# Top.net
KiCad netlist of a schematic drawn in Altium Designer
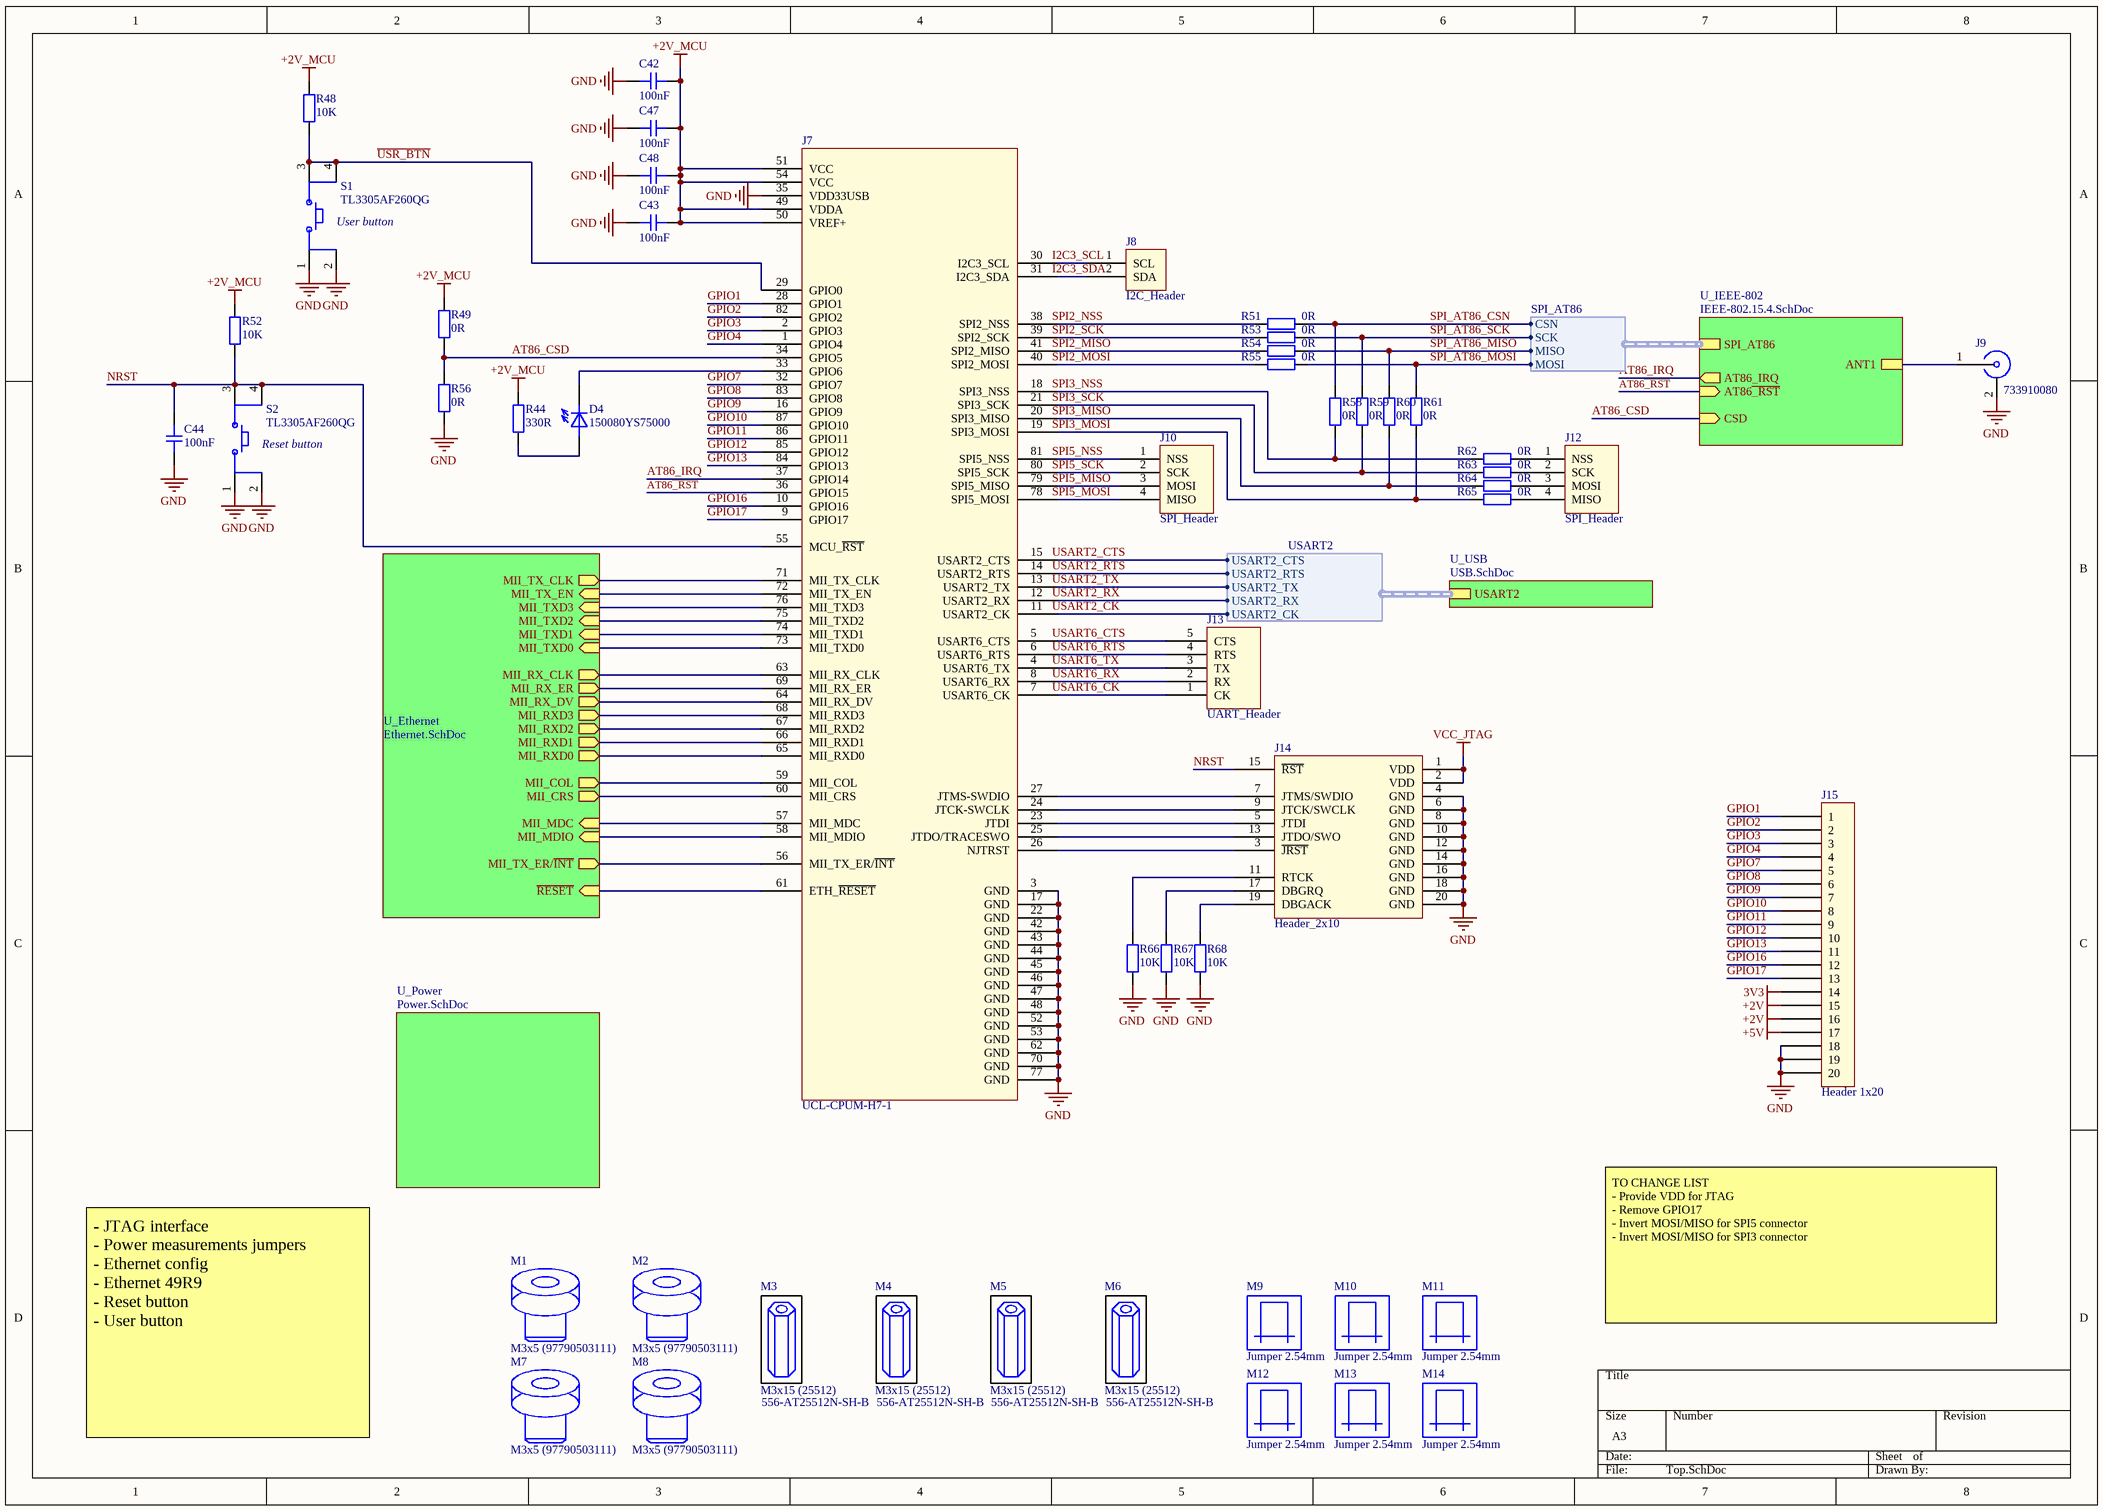
[diagram p0: Top.SchDoc]

(export (version "E")
  (design (tool "Eeschema 10.0.6"))
  (components
    (comp (ref "C42")
      (value "100nF")
      (footprint "Capacitor-0603")
      (fields (field (name "Comment") "C-100nF-0603"))
      (libsource (lib "Components") (part "C-100nF-0603"))
    )
    (comp (ref "C43")
      (value "100nF")
      (footprint "Capacitor-0603")
      (fields (field (name "Comment") "C-100nF-0603"))
      (libsource (lib "Components") (part "C-100nF-0603"))
    )
    (comp (ref "C44")
      (value "100nF")
      (footprint "Capacitor-0603")
      (fields (field (name "Comment") "C-100nF-0603"))
      (libsource (lib "Components") (part "C-100nF-0603"))
    )
    (comp (ref "C47")
      (value "100nF")
      (footprint "Capacitor-0603")
      (fields (field (name "Comment") "C-100nF-0603"))
      (libsource (lib "Components") (part "C-100nF-0603"))
    )
    (comp (ref "C48")
      (value "100nF")
      (footprint "Capacitor-0603")
      (fields (field (name "Comment") "C-100nF-0603"))
      (libsource (lib "Components") (part "C-100nF-0603"))
    )
    (comp (ref "D4")
      (value "150080YS75000")
      (footprint "150080YS75000")
      (libsource (lib "Components") (part "150080YS75000"))
    )
    (comp (ref "J7")
      (value "UCL-CPUM-H7-1")
      (footprint "UCL-CPUM-H7-1")
      (libsource (lib "Components") (part "UCL-CPUM-H7-1"))
    )
    (comp (ref "J8")
      (value "I2C_Header")
      (footprint "I2C_header")
      (libsource (lib "Components") (part "I2C_Header"))
    )
    (comp (ref "J9")
      (value "733910080")
      (footprint "SMA_733910080")
      (libsource (lib "Components") (part "SMA_733910080"))
    )
    (comp (ref "J10")
      (value "SPI_Header")
      (footprint "SPI_Header")
      (libsource (lib "Components") (part "SPI_Header"))
    )
    (comp (ref "J12")
      (value "SPI_Header")
      (footprint "SPI_Header")
      (libsource (lib "Components") (part "SPI_Header"))
    )
    (comp (ref "J13")
      (value "UART_Header")
      (footprint "UART_Header")
      (libsource (lib "Components") (part "UART_Header"))
    )
    (comp (ref "J14")
      (value "Header_2x10")
      (footprint "JTAG_Header")
      (libsource (lib "Components") (part "JTAG_Header"))
    )
    (comp (ref "J15")
      (value "Header 1x20")
      (footprint "GPIO_Header")
      (libsource (lib "Components") (part "GPIO_Header"))
    )
    (comp (ref "M1")
      (value "M3x5 (97790503111)")
      (footprint "Screw_M3")
      (libsource (lib "Components") (part "Screw_M3x5"))
    )
    (comp (ref "M2")
      (value "M3x5 (97790503111)")
      (footprint "Screw_M3")
      (libsource (lib "Components") (part "Screw_M3x5"))
    )
    (comp (ref "M3")
      (value "M3x15 (25512)")
      (fields (field (name "SUPPLIER PART NUMBER 1") "556-AT25512N-SH-B"))
      (libsource (lib "Components") (part "Standoff_hex_M3_15mm_25512"))
    )
    (comp (ref "M4")
      (value "M3x15 (25512)")
      (fields (field (name "SUPPLIER PART NUMBER 1") "556-AT25512N-SH-B"))
      (libsource (lib "Components") (part "Standoff_hex_M3_15mm_25512"))
    )
    (comp (ref "M5")
      (value "M3x15 (25512)")
      (fields (field (name "SUPPLIER PART NUMBER 1") "556-AT25512N-SH-B"))
      (libsource (lib "Components") (part "Standoff_hex_M3_15mm_25512"))
    )
    (comp (ref "M6")
      (value "M3x15 (25512)")
      (fields (field (name "SUPPLIER PART NUMBER 1") "556-AT25512N-SH-B"))
      (libsource (lib "Components") (part "Standoff_hex_M3_15mm_25512"))
    )
    (comp (ref "M7")
      (value "M3x5 (97790503111)")
      (footprint "Screw_M3")
      (libsource (lib "Components") (part "Screw_M3x5"))
    )
    (comp (ref "M8")
      (value "M3x5 (97790503111)")
      (footprint "Screw_M3")
      (libsource (lib "Components") (part "Screw_M3x5"))
    )
    (comp (ref "M9") (value "Jumper 2.54mm") (libsource (lib "Components") (part "QPC02SXGN-RC")))
    (comp (ref "M10") (value "Jumper 2.54mm") (libsource (lib "Components") (part "QPC02SXGN-RC")))
    (comp (ref "M11") (value "Jumper 2.54mm") (libsource (lib "Components") (part "QPC02SXGN-RC")))
    (comp (ref "M12") (value "Jumper 2.54mm") (libsource (lib "Components") (part "QPC02SXGN-RC")))
    (comp (ref "M13") (value "Jumper 2.54mm") (libsource (lib "Components") (part "QPC02SXGN-RC")))
    (comp (ref "M14") (value "Jumper 2.54mm") (libsource (lib "Components") (part "QPC02SXGN-RC")))
    (comp (ref "R44")
      (value "330R")
      (footprint "Resistor-0603")
      (fields (field (name "Comment") "R-330R-0603"))
      (libsource (lib "Components") (part "R-330R-0603"))
    )
    (comp (ref "R48")
      (value "10K")
      (footprint "Resistor-0603")
      (fields (field (name "Comment") "R-10K-0603"))
      (libsource (lib "Components") (part "R-10K-0603"))
    )
    (comp (ref "R49")
      (value "0R")
      (footprint "Resistor-0603")
      (fields (field (name "Comment") "R-0R-0603"))
      (libsource (lib "Components") (part "R-0R-0603"))
    )
    (comp (ref "R51")
      (value "0R")
      (footprint "Resistor-0603")
      (fields (field (name "Comment") "R-0R-0603"))
      (libsource (lib "Components") (part "R-0R-0603"))
    )
    (comp (ref "R52")
      (value "10K")
      (footprint "Resistor-0603")
      (fields (field (name "Comment") "R-10K-0603"))
      (libsource (lib "Components") (part "R-10K-0603"))
    )
    (comp (ref "R53")
      (value "0R")
      (footprint "Resistor-0603")
      (fields (field (name "Comment") "R-0R-0603"))
      (libsource (lib "Components") (part "R-0R-0603"))
    )
    (comp (ref "R54")
      (value "0R")
      (footprint "Resistor-0603")
      (fields (field (name "Comment") "R-0R-0603"))
      (libsource (lib "Components") (part "R-0R-0603"))
    )
    (comp (ref "R55")
      (value "0R")
      (footprint "Resistor-0603")
      (fields (field (name "Comment") "R-0R-0603"))
      (libsource (lib "Components") (part "R-0R-0603"))
    )
    (comp (ref "R56")
      (value "0R")
      (footprint "Resistor-0603")
      (fields (field (name "Comment") "R-0R-0603"))
      (libsource (lib "Components") (part "R-0R-0603"))
    )
    (comp (ref "R58")
      (value "0R")
      (footprint "Resistor-0603")
      (fields (field (name "Comment") "R-0R-0603"))
      (libsource (lib "Components") (part "R-0R-0603"))
    )
    (comp (ref "R59")
      (value "0R")
      (footprint "Resistor-0603")
      (fields (field (name "Comment") "R-0R-0603"))
      (libsource (lib "Components") (part "R-0R-0603"))
    )
    (comp (ref "R60")
      (value "0R")
      (footprint "Resistor-0603")
      (fields (field (name "Comment") "R-0R-0603"))
      (libsource (lib "Components") (part "R-0R-0603"))
    )
    (comp (ref "R61")
      (value "0R")
      (footprint "Resistor-0603")
      (fields (field (name "Comment") "R-0R-0603"))
      (libsource (lib "Components") (part "R-0R-0603"))
    )
    (comp (ref "R62")
      (value "0R")
      (footprint "Resistor-0603")
      (fields (field (name "Comment") "R-0R-0603"))
      (libsource (lib "Components") (part "R-0R-0603"))
    )
    (comp (ref "R63")
      (value "0R")
      (footprint "Resistor-0603")
      (fields (field (name "Comment") "R-0R-0603"))
      (libsource (lib "Components") (part "R-0R-0603"))
    )
    (comp (ref "R64")
      (value "0R")
      (footprint "Resistor-0603")
      (fields (field (name "Comment") "R-0R-0603"))
      (libsource (lib "Components") (part "R-0R-0603"))
    )
    (comp (ref "R65")
      (value "0R")
      (footprint "Resistor-0603")
      (fields (field (name "Comment") "R-0R-0603"))
      (libsource (lib "Components") (part "R-0R-0603"))
    )
    (comp (ref "R66")
      (value "10K")
      (footprint "Resistor-0603")
      (fields (field (name "Comment") "R-10K-0603"))
      (libsource (lib "Components") (part "R-10K-0603"))
    )
    (comp (ref "R67")
      (value "10K")
      (footprint "Resistor-0603")
      (fields (field (name "Comment") "R-10K-0603"))
      (libsource (lib "Components") (part "R-10K-0603"))
    )
    (comp (ref "R68")
      (value "10K")
      (footprint "Resistor-0603")
      (fields (field (name "Comment") "R-10K-0603"))
      (libsource (lib "Components") (part "R-10K-0603"))
    )
    (comp (ref "S1")
      (value "TL3305AF260QG")
      (footprint "TL3305AF260QG")
      (libsource (lib "Components") (part "TL3305AF260QG"))
    )
    (comp (ref "S2")
      (value "TL3305AF260QG")
      (footprint "TL3305AF260QG")
      (libsource (lib "Components") (part "TL3305AF260QG"))
    )
  )
  (nets
    (net (code "3") (name "+2V") (class "Default")
      (node (ref "J15") (pin "15") (pinfunction "15_15") (pintype "passive"))
      (node (ref "J15") (pin "16") (pinfunction "16_16") (pintype "passive"))
    )
    (net (code "4") (name "+2V_MCU") (class "Default")
      (node (ref "C42") (pin "2") (pinfunction "2_2") (pintype "passive"))
      (node (ref "C43") (pin "2") (pinfunction "2_2") (pintype "passive"))
      (node (ref "C47") (pin "2") (pinfunction "2_2") (pintype "passive"))
      (node (ref "C48") (pin "2") (pinfunction "2_2") (pintype "passive"))
      (node (ref "J7") (pin "49") (pinfunction "VDDA_49") (pintype "passive"))
      (node (ref "J7") (pin "50") (pinfunction "VREF+_50") (pintype "passive"))
      (node (ref "J7") (pin "51") (pinfunction "VCC_51") (pintype "passive"))
      (node (ref "J7") (pin "54") (pinfunction "VCC_54") (pintype "passive"))
      (node (ref "R44") (pin "2") (pinfunction "2_2") (pintype "passive"))
      (node (ref "R48") (pin "2") (pinfunction "2_2") (pintype "passive"))
      (node (ref "R49") (pin "2") (pinfunction "2_2") (pintype "passive"))
      (node (ref "R52") (pin "2") (pinfunction "2_2") (pintype "passive"))
    )
    (net (code "5") (name "+5V") (class "Default")
      (node (ref "J15") (pin "17") (pinfunction "17_17") (pintype "passive"))
    )
    (net (code "6") (name "/ANT1") (class "Default")
      (node (ref "J9") (pin "1") (pinfunction "SIG_1") (pintype "passive"))
    )
    (net (code "7") (name "/AT86_CSD") (class "Default")
      (node (ref "J7") (pin "34") (pinfunction "GPIO5_34") (pintype "passive"))
      (node (ref "R49") (pin "1") (pinfunction "1_1") (pintype "passive"))
      (node (ref "R56") (pin "2") (pinfunction "2_2") (pintype "passive"))
    )
    (net (code "8") (name "/AT86_IRQ") (class "Default")
      (node (ref "J7") (pin "37") (pinfunction "GPIO14_37") (pintype "passive"))
    )
    (net (code "9") (name "/AT86~{_RST}") (class "Default")
      (node (ref "J7") (pin "36") (pinfunction "GPIO15_36") (pintype "passive"))
    )
    (net (code "10") (name "/GPIO1") (class "Default")
      (node (ref "J15") (pin "1") (pinfunction "1_1") (pintype "passive"))
      (node (ref "J7") (pin "28") (pinfunction "GPIO1_28") (pintype "passive"))
    )
    (net (code "11") (name "/GPIO2") (class "Default")
      (node (ref "J15") (pin "2") (pinfunction "2_2") (pintype "passive"))
      (node (ref "J7") (pin "82") (pinfunction "GPIO2_82") (pintype "passive"))
    )
    (net (code "12") (name "/GPIO3") (class "Default")
      (node (ref "J15") (pin "3") (pinfunction "3_3") (pintype "passive"))
      (node (ref "J7") (pin "2") (pinfunction "GPIO3_2") (pintype "passive"))
    )
    (net (code "13") (name "/GPIO4") (class "Default")
      (node (ref "J15") (pin "4") (pinfunction "4_4") (pintype "passive"))
      (node (ref "J7") (pin "1") (pinfunction "GPIO4_1") (pintype "passive"))
    )
    (net (code "14") (name "/GPIO7") (class "Default")
      (node (ref "J15") (pin "5") (pinfunction "5_5") (pintype "passive"))
      (node (ref "J7") (pin "32") (pinfunction "GPIO7_32") (pintype "passive"))
    )
    (net (code "15") (name "/GPIO8") (class "Default")
      (node (ref "J15") (pin "6") (pinfunction "6_6") (pintype "passive"))
      (node (ref "J7") (pin "83") (pinfunction "GPIO8_83") (pintype "passive"))
    )
    (net (code "16") (name "/GPIO9") (class "Default")
      (node (ref "J15") (pin "7") (pinfunction "7_7") (pintype "passive"))
      (node (ref "J7") (pin "16") (pinfunction "GPIO9_16") (pintype "passive"))
    )
    (net (code "17") (name "/GPIO10") (class "Default")
      (node (ref "J15") (pin "8") (pinfunction "8_8") (pintype "passive"))
      (node (ref "J7") (pin "87") (pinfunction "GPIO10_87") (pintype "passive"))
    )
    (net (code "18") (name "/GPIO11") (class "Default")
      (node (ref "J15") (pin "9") (pinfunction "9_9") (pintype "passive"))
      (node (ref "J7") (pin "86") (pinfunction "GPIO11_86") (pintype "passive"))
    )
    (net (code "19") (name "/GPIO12") (class "Default")
      (node (ref "J15") (pin "10") (pinfunction "10_10") (pintype "passive"))
      (node (ref "J7") (pin "85") (pinfunction "GPIO12_85") (pintype "passive"))
    )
    (net (code "20") (name "/GPIO13") (class "Default")
      (node (ref "J15") (pin "11") (pinfunction "11_11") (pintype "passive"))
      (node (ref "J7") (pin "84") (pinfunction "GPIO13_84") (pintype "passive"))
    )
    (net (code "21") (name "/GPIO16") (class "Default")
      (node (ref "J15") (pin "12") (pinfunction "12_12") (pintype "passive"))
      (node (ref "J7") (pin "10") (pinfunction "GPIO16_10") (pintype "passive"))
    )
    (net (code "22") (name "/GPIO17") (class "Default")
      (node (ref "J15") (pin "13") (pinfunction "13_13") (pintype "passive"))
      (node (ref "J7") (pin "9") (pinfunction "GPIO17_9") (pintype "passive"))
    )
    (net (code "25") (name "/MII_COL") (class "Default")
      (node (ref "J7") (pin "59") (pinfunction "MII_COL_59") (pintype "passive"))
    )
    (net (code "26") (name "/MII_CRS") (class "Default")
      (node (ref "J7") (pin "60") (pinfunction "MII_CRS_60") (pintype "passive"))
    )
    (net (code "27") (name "/MII_MDC") (class "Default")
      (node (ref "J7") (pin "57") (pinfunction "MII_MDC_57") (pintype "passive"))
    )
    (net (code "28") (name "/MII_MDIO") (class "Default")
      (node (ref "J7") (pin "58") (pinfunction "MII_MDIO_58") (pintype "passive"))
    )
    (net (code "29") (name "/MII_RXD0") (class "Default")
      (node (ref "J7") (pin "65") (pinfunction "MII_RXD0_65") (pintype "passive"))
    )
    (net (code "30") (name "/MII_RXD1") (class "Default")
      (node (ref "J7") (pin "66") (pinfunction "MII_RXD1_66") (pintype "passive"))
    )
    (net (code "31") (name "/MII_RXD2") (class "Default")
      (node (ref "J7") (pin "67") (pinfunction "MII_RXD2_67") (pintype "passive"))
    )
    (net (code "32") (name "/MII_RXD3") (class "Default")
      (node (ref "J7") (pin "68") (pinfunction "MII_RXD3_68") (pintype "passive"))
    )
    (net (code "33") (name "/MII_RX_CLK") (class "Default")
      (node (ref "J7") (pin "63") (pinfunction "MII_RX_CLK_63") (pintype "passive"))
    )
    (net (code "34") (name "/MII_RX_DV") (class "Default")
      (node (ref "J7") (pin "64") (pinfunction "MII_RX_DV_64") (pintype "passive"))
    )
    (net (code "35") (name "/MII_RX_ER") (class "Default")
      (node (ref "J7") (pin "69") (pinfunction "MII_RX_ER_69") (pintype "passive"))
    )
    (net (code "36") (name "/MII_TXD0") (class "Default")
      (node (ref "J7") (pin "73") (pinfunction "MII_TXD0_73") (pintype "passive"))
    )
    (net (code "37") (name "/MII_TXD1") (class "Default")
      (node (ref "J7") (pin "74") (pinfunction "MII_TXD1_74") (pintype "passive"))
    )
    (net (code "38") (name "/MII_TXD2") (class "Default")
      (node (ref "J7") (pin "75") (pinfunction "MII_TXD2_75") (pintype "passive"))
    )
    (net (code "39") (name "/MII_TXD3") (class "Default")
      (node (ref "J7") (pin "76") (pinfunction "MII_TXD3_76") (pintype "passive"))
    )
    (net (code "40") (name "/MII_TX_CLK") (class "Default")
      (node (ref "J7") (pin "71") (pinfunction "MII_TX_CLK_71") (pintype "passive"))
    )
    (net (code "41") (name "/MII_TX_EN") (class "Default")
      (node (ref "J7") (pin "72") (pinfunction "MII_TX_EN_72") (pintype "passive"))
    )
    (net (code "42") (name "/MII_TX_ER{slash}~{INT}") (class "Default")
      (node (ref "J7") (pin "56") (pinfunction "MII_TX_ER/~{INT}_56") (pintype "passive"))
    )
    (net (code "43") (name "/NRST") (class "Default")
      (node (ref "C44") (pin "2") (pinfunction "2_2") (pintype "passive"))
      (node (ref "J14") (pin "15") (pinfunction "~{RST}_15") (pintype "passive"))
      (node (ref "J7") (pin "55") (pinfunction "MCU_~{RST}_55") (pintype "passive"))
      (node (ref "R52") (pin "1") (pinfunction "1_1") (pintype "passive"))
      (node (ref "S2") (pin "3") (pinfunction "3_3") (pintype "passive"))
      (node (ref "S2") (pin "4") (pinfunction "4_4") (pintype "passive"))
    )
    (net (code "56") (name "/SPI_AT86_CSN") (class "Default")
      (node (ref "R51") (pin "2") (pinfunction "2_2") (pintype "passive"))
      (node (ref "R58") (pin "2") (pinfunction "2_2") (pintype "passive"))
    )
    (net (code "57") (name "/SPI_AT86_MISO") (class "Default")
      (node (ref "R54") (pin "2") (pinfunction "2_2") (pintype "passive"))
      (node (ref "R60") (pin "2") (pinfunction "2_2") (pintype "passive"))
    )
    (net (code "58") (name "/SPI_AT86_MOSI") (class "Default")
      (node (ref "R55") (pin "2") (pinfunction "2_2") (pintype "passive"))
      (node (ref "R61") (pin "2") (pinfunction "2_2") (pintype "passive"))
    )
    (net (code "59") (name "/SPI_AT86_SCK") (class "Default")
      (node (ref "R53") (pin "2") (pinfunction "2_2") (pintype "passive"))
      (node (ref "R59") (pin "2") (pinfunction "2_2") (pintype "passive"))
    )
    (net (code "72") (name "/~{RESET}") (class "Default")
      (node (ref "J7") (pin "61") (pinfunction "ETH_~{RESET}_61") (pintype "passive"))
    )
    (net (code "73") (name "/~{USR_BTN}") (class "Default")
      (node (ref "J7") (pin "29") (pinfunction "GPIO0_29") (pintype "passive"))
      (node (ref "R48") (pin "1") (pinfunction "1_1") (pintype "passive"))
      (node (ref "S1") (pin "3") (pinfunction "3_3") (pintype "passive"))
      (node (ref "S1") (pin "4") (pinfunction "4_4") (pintype "passive"))
    )
    (net (code "74") (name "3V3") (class "Default")
      (node (ref "J15") (pin "14") (pinfunction "14_14") (pintype "passive"))
    )
    (net (code "75") (name "GND") (class "Default")
      (node (ref "C42") (pin "1") (pinfunction "1_1") (pintype "passive"))
      (node (ref "C43") (pin "1") (pinfunction "1_1") (pintype "passive"))
      (node (ref "C44") (pin "1") (pinfunction "1_1") (pintype "passive"))
      (node (ref "C47") (pin "1") (pinfunction "1_1") (pintype "passive"))
      (node (ref "C48") (pin "1") (pinfunction "1_1") (pintype "passive"))
      (node (ref "J14") (pin "10") (pinfunction "GND_10") (pintype "passive"))
      (node (ref "J14") (pin "12") (pinfunction "GND_12") (pintype "passive"))
      (node (ref "J14") (pin "14") (pinfunction "GND_14") (pintype "passive"))
      (node (ref "J14") (pin "16") (pinfunction "GND_16") (pintype "passive"))
      (node (ref "J14") (pin "18") (pinfunction "GND_18") (pintype "passive"))
      (node (ref "J14") (pin "20") (pinfunction "GND_20") (pintype "passive"))
      (node (ref "J14") (pin "4") (pinfunction "GND_4") (pintype "passive"))
      (node (ref "J14") (pin "6") (pinfunction "GND_6") (pintype "passive"))
      (node (ref "J14") (pin "8") (pinfunction "GND_8") (pintype "passive"))
      (node (ref "J15") (pin "18") (pinfunction "18_18") (pintype "passive"))
      (node (ref "J15") (pin "19") (pinfunction "19_19") (pintype "passive"))
      (node (ref "J15") (pin "20") (pinfunction "20_20") (pintype "passive"))
      (node (ref "J7") (pin "17") (pinfunction "GND_17") (pintype "passive"))
      (node (ref "J7") (pin "22") (pinfunction "GND_22") (pintype "passive"))
      (node (ref "J7") (pin "3") (pinfunction "GND_3") (pintype "passive"))
      (node (ref "J7") (pin "35") (pinfunction "VDD33USB_35") (pintype "passive"))
      (node (ref "J7") (pin "42") (pinfunction "GND_42") (pintype "passive"))
      (node (ref "J7") (pin "43") (pinfunction "GND_43") (pintype "passive"))
      (node (ref "J7") (pin "44") (pinfunction "GND_44") (pintype "passive"))
      (node (ref "J7") (pin "45") (pinfunction "GND_45") (pintype "passive"))
      (node (ref "J7") (pin "46") (pinfunction "GND_46") (pintype "passive"))
      (node (ref "J7") (pin "47") (pinfunction "GND_47") (pintype "passive"))
      (node (ref "J7") (pin "48") (pinfunction "GND_48") (pintype "passive"))
      (node (ref "J7") (pin "52") (pinfunction "GND_52") (pintype "passive"))
      (node (ref "J7") (pin "53") (pinfunction "GND_53") (pintype "passive"))
      (node (ref "J7") (pin "62") (pinfunction "GND_62") (pintype "passive"))
      (node (ref "J7") (pin "70") (pinfunction "GND_70") (pintype "passive"))
      (node (ref "J7") (pin "77") (pinfunction "GND_77") (pintype "passive"))
      (node (ref "J9") (pin "2") (pinfunction "GND_2") (pintype "passive"))
      (node (ref "R56") (pin "1") (pinfunction "1_1") (pintype "passive"))
      (node (ref "R66") (pin "1") (pinfunction "1_1") (pintype "passive"))
      (node (ref "R67") (pin "1") (pinfunction "1_1") (pintype "passive"))
      (node (ref "R68") (pin "1") (pinfunction "1_1") (pintype "passive"))
      (node (ref "S1") (pin "1") (pinfunction "1_1") (pintype "passive"))
      (node (ref "S1") (pin "2") (pinfunction "2_2") (pintype "passive"))
      (node (ref "S2") (pin "1") (pinfunction "1_1") (pintype "passive"))
      (node (ref "S2") (pin "2") (pinfunction "2_2") (pintype "passive"))
    )
    (net (code "76") (name "Net-(D4-Pad2)") (class "Default")
      (node (ref "D4") (pin "2") (pinfunction "2_2") (pintype "passive"))
      (node (ref "R44") (pin "1") (pinfunction "1_1") (pintype "passive"))
    )
    (net (code "77") (name "Net-(J7-GPIO6)") (class "Default")
      (node (ref "D4") (pin "1") (pinfunction "1_1") (pintype "passive"))
      (node (ref "J7") (pin "33") (pinfunction "GPIO6_33") (pintype "passive"))
    )
    (net (code "78") (name "Net-(J7-I2C3_SCL)") (class "Default")
      (node (ref "J7") (pin "30") (pinfunction "I2C3_SCL_30") (pintype "passive"))
      (node (ref "J8") (pin "1") (pinfunction "SCL_1") (pintype "passive"))
    )
    (net (code "79") (name "Net-(J7-I2C3_SDA)") (class "Default")
      (node (ref "J7") (pin "31") (pinfunction "I2C3_SDA_31") (pintype "passive"))
      (node (ref "J8") (pin "2") (pinfunction "SDA_2") (pintype "passive"))
    )
    (net (code "80") (name "Net-(J7-SPI2_MISO)") (class "Default")
      (node (ref "J7") (pin "41") (pinfunction "SPI2_MISO_41") (pintype "passive"))
      (node (ref "R54") (pin "1") (pinfunction "1_1") (pintype "passive"))
    )
    (net (code "81") (name "Net-(J7-SPI2_MOSI)") (class "Default")
      (node (ref "J7") (pin "40") (pinfunction "SPI2_MOSI_40") (pintype "passive"))
      (node (ref "R55") (pin "1") (pinfunction "1_1") (pintype "passive"))
    )
    (net (code "82") (name "Net-(J7-SPI2_NSS)") (class "Default")
      (node (ref "J7") (pin "38") (pinfunction "SPI2_NSS_38") (pintype "passive"))
      (node (ref "R51") (pin "1") (pinfunction "1_1") (pintype "passive"))
    )
    (net (code "83") (name "Net-(J7-SPI2_SCK)") (class "Default")
      (node (ref "J7") (pin "39") (pinfunction "SPI2_SCK_39") (pintype "passive"))
      (node (ref "R53") (pin "1") (pinfunction "1_1") (pintype "passive"))
    )
    (net (code "84") (name "Net-(J7-SPI3_MISO)") (class "Default")
      (node (ref "J7") (pin "20") (pinfunction "SPI3_MISO_20") (pintype "passive"))
      (node (ref "R60") (pin "1") (pinfunction "1_1") (pintype "passive"))
      (node (ref "R64") (pin "1") (pinfunction "1_1") (pintype "passive"))
    )
    (net (code "85") (name "Net-(J7-SPI3_MOSI)") (class "Default")
      (node (ref "J7") (pin "19") (pinfunction "SPI3_MOSI_19") (pintype "passive"))
      (node (ref "R61") (pin "1") (pinfunction "1_1") (pintype "passive"))
      (node (ref "R65") (pin "1") (pinfunction "1_1") (pintype "passive"))
    )
    (net (code "86") (name "Net-(J7-SPI3_NSS)") (class "Default")
      (node (ref "J7") (pin "18") (pinfunction "SPI3_NSS_18") (pintype "passive"))
      (node (ref "R58") (pin "1") (pinfunction "1_1") (pintype "passive"))
      (node (ref "R62") (pin "1") (pinfunction "1_1") (pintype "passive"))
    )
    (net (code "87") (name "Net-(J7-SPI3_SCK)") (class "Default")
      (node (ref "J7") (pin "21") (pinfunction "SPI3_SCK_21") (pintype "passive"))
      (node (ref "R59") (pin "1") (pinfunction "1_1") (pintype "passive"))
      (node (ref "R63") (pin "1") (pinfunction "1_1") (pintype "passive"))
    )
    (net (code "88") (name "Net-(J10-MISO)") (class "Default")
      (node (ref "J10") (pin "4") (pinfunction "MISO_4") (pintype "passive"))
      (node (ref "J7") (pin "78") (pinfunction "SPI5_MOSI_78") (pintype "passive"))
    )
    (net (code "89") (name "Net-(J10-MOSI)") (class "Default")
      (node (ref "J10") (pin "3") (pinfunction "MOSI_3") (pintype "passive"))
      (node (ref "J7") (pin "79") (pinfunction "SPI5_MISO_79") (pintype "passive"))
    )
    (net (code "90") (name "Net-(J10-NSS)") (class "Default")
      (node (ref "J10") (pin "1") (pinfunction "NSS_1") (pintype "passive"))
      (node (ref "J7") (pin "81") (pinfunction "SPI5_NSS_81") (pintype "passive"))
    )
    (net (code "91") (name "Net-(J10-SCK)") (class "Default")
      (node (ref "J10") (pin "2") (pinfunction "SCK_2") (pintype "passive"))
      (node (ref "J7") (pin "80") (pinfunction "SPI5_SCK_80") (pintype "passive"))
    )
    (net (code "92") (name "Net-(J12-MISO)") (class "Default")
      (node (ref "J12") (pin "4") (pinfunction "MISO_4") (pintype "passive"))
      (node (ref "R65") (pin "2") (pinfunction "2_2") (pintype "passive"))
    )
    (net (code "93") (name "Net-(J12-MOSI)") (class "Default")
      (node (ref "J12") (pin "3") (pinfunction "MOSI_3") (pintype "passive"))
      (node (ref "R64") (pin "2") (pinfunction "2_2") (pintype "passive"))
    )
    (net (code "94") (name "Net-(J12-NSS)") (class "Default")
      (node (ref "J12") (pin "1") (pinfunction "NSS_1") (pintype "passive"))
      (node (ref "R62") (pin "2") (pinfunction "2_2") (pintype "passive"))
    )
    (net (code "95") (name "Net-(J12-SCK)") (class "Default")
      (node (ref "J12") (pin "2") (pinfunction "SCK_2") (pintype "passive"))
      (node (ref "R63") (pin "2") (pinfunction "2_2") (pintype "passive"))
    )
    (net (code "96") (name "Net-(J13-CK)") (class "Default")
      (node (ref "J13") (pin "1") (pinfunction "CK_1") (pintype "passive"))
      (node (ref "J7") (pin "7") (pinfunction "USART6_CK_7") (pintype "passive"))
    )
    (net (code "97") (name "Net-(J13-CTS)") (class "Default")
      (node (ref "J13") (pin "5") (pinfunction "CTS_5") (pintype "passive"))
      (node (ref "J7") (pin "5") (pinfunction "USART6_CTS_5") (pintype "passive"))
    )
    (net (code "98") (name "Net-(J13-RTS)") (class "Default")
      (node (ref "J13") (pin "4") (pinfunction "RTS_4") (pintype "passive"))
      (node (ref "J7") (pin "6") (pinfunction "USART6_RTS_6") (pintype "passive"))
    )
    (net (code "99") (name "Net-(J13-RX)") (class "Default")
      (node (ref "J13") (pin "2") (pinfunction "RX_2") (pintype "passive"))
      (node (ref "J7") (pin "8") (pinfunction "USART6_RX_8") (pintype "passive"))
    )
    (net (code "100") (name "Net-(J13-TX)") (class "Default")
      (node (ref "J13") (pin "3") (pinfunction "TX_3") (pintype "passive"))
      (node (ref "J7") (pin "4") (pinfunction "USART6_TX_4") (pintype "passive"))
    )
    (net (code "101") (name "Net-(J14-DBGACK)") (class "Default")
      (node (ref "J14") (pin "19") (pinfunction "DBGACK_19") (pintype "passive"))
      (node (ref "R68") (pin "2") (pinfunction "2_2") (pintype "passive"))
    )
    (net (code "102") (name "Net-(J14-DBGRQ)") (class "Default")
      (node (ref "J14") (pin "17") (pinfunction "DBGRQ_17") (pintype "passive"))
      (node (ref "R67") (pin "2") (pinfunction "2_2") (pintype "passive"))
    )
    (net (code "103") (name "Net-(J14-JTCK{slash}SWCLK)") (class "Default")
      (node (ref "J14") (pin "9") (pinfunction "JTCK/SWCLK_9") (pintype "passive"))
      (node (ref "J7") (pin "24") (pinfunction "JTCK-SWCLK_24") (pintype "passive"))
    )
    (net (code "104") (name "Net-(J14-JTDI)") (class "Default")
      (node (ref "J14") (pin "5") (pinfunction "JTDI_5") (pintype "passive"))
      (node (ref "J7") (pin "23") (pinfunction "JTDI_23") (pintype "passive"))
    )
    (net (code "105") (name "Net-(J14-JTDO{slash}SWO)") (class "Default")
      (node (ref "J14") (pin "13") (pinfunction "JTDO/SWO_13") (pintype "passive"))
      (node (ref "J7") (pin "25") (pinfunction "JTDO/TRACESWO_25") (pintype "passive"))
    )
    (net (code "106") (name "Net-(J14-JTMS{slash}SWDIO)") (class "Default")
      (node (ref "J14") (pin "7") (pinfunction "JTMS/SWDIO_7") (pintype "passive"))
      (node (ref "J7") (pin "27") (pinfunction "JTMS-SWDIO_27") (pintype "passive"))
    )
    (net (code "107") (name "Net-(J14-RTCK)") (class "Default")
      (node (ref "J14") (pin "11") (pinfunction "RTCK_11") (pintype "passive"))
      (node (ref "R66") (pin "2") (pinfunction "2_2") (pintype "passive"))
    )
    (net (code "108") (name "Net-(J14-~{JRST})") (class "Default")
      (node (ref "J14") (pin "3") (pinfunction "~{JRST}_3") (pintype "passive"))
      (node (ref "J7") (pin "26") (pinfunction "NJTRST_26") (pintype "passive"))
    )
    (net (code "109") (name "VCC_JTAG") (class "Default")
      (node (ref "J14") (pin "1") (pinfunction "VDD_1") (pintype "passive"))
      (node (ref "J14") (pin "2") (pinfunction "VDD_2") (pintype "passive"))
    )
    (net (code "110") (name "unconnected-(J7-USART2_CK-Pad11)") (class "Default")
      (node (ref "J7") (pin "11") (pinfunction "USART2_CK_11") (pintype "passive"))
    )
    (net (code "111") (name "unconnected-(J7-USART2_CTS-Pad15)") (class "Default")
      (node (ref "J7") (pin "15") (pinfunction "USART2_CTS_15") (pintype "passive"))
    )
    (net (code "112") (name "unconnected-(J7-USART2_RTS-Pad14)") (class "Default")
      (node (ref "J7") (pin "14") (pinfunction "USART2_RTS_14") (pintype "passive"))
    )
    (net (code "113") (name "unconnected-(J7-USART2_RX-Pad12)") (class "Default")
      (node (ref "J7") (pin "12") (pinfunction "USART2_RX_12") (pintype "passive"))
    )
    (net (code "114") (name "unconnected-(J7-USART2_TX-Pad13)") (class "Default")
      (node (ref "J7") (pin "13") (pinfunction "USART2_TX_13") (pintype "passive"))
    )
  )
)
